# InterfaceBoard.net
KiCad netlist of a schematic drawn in EAGLE
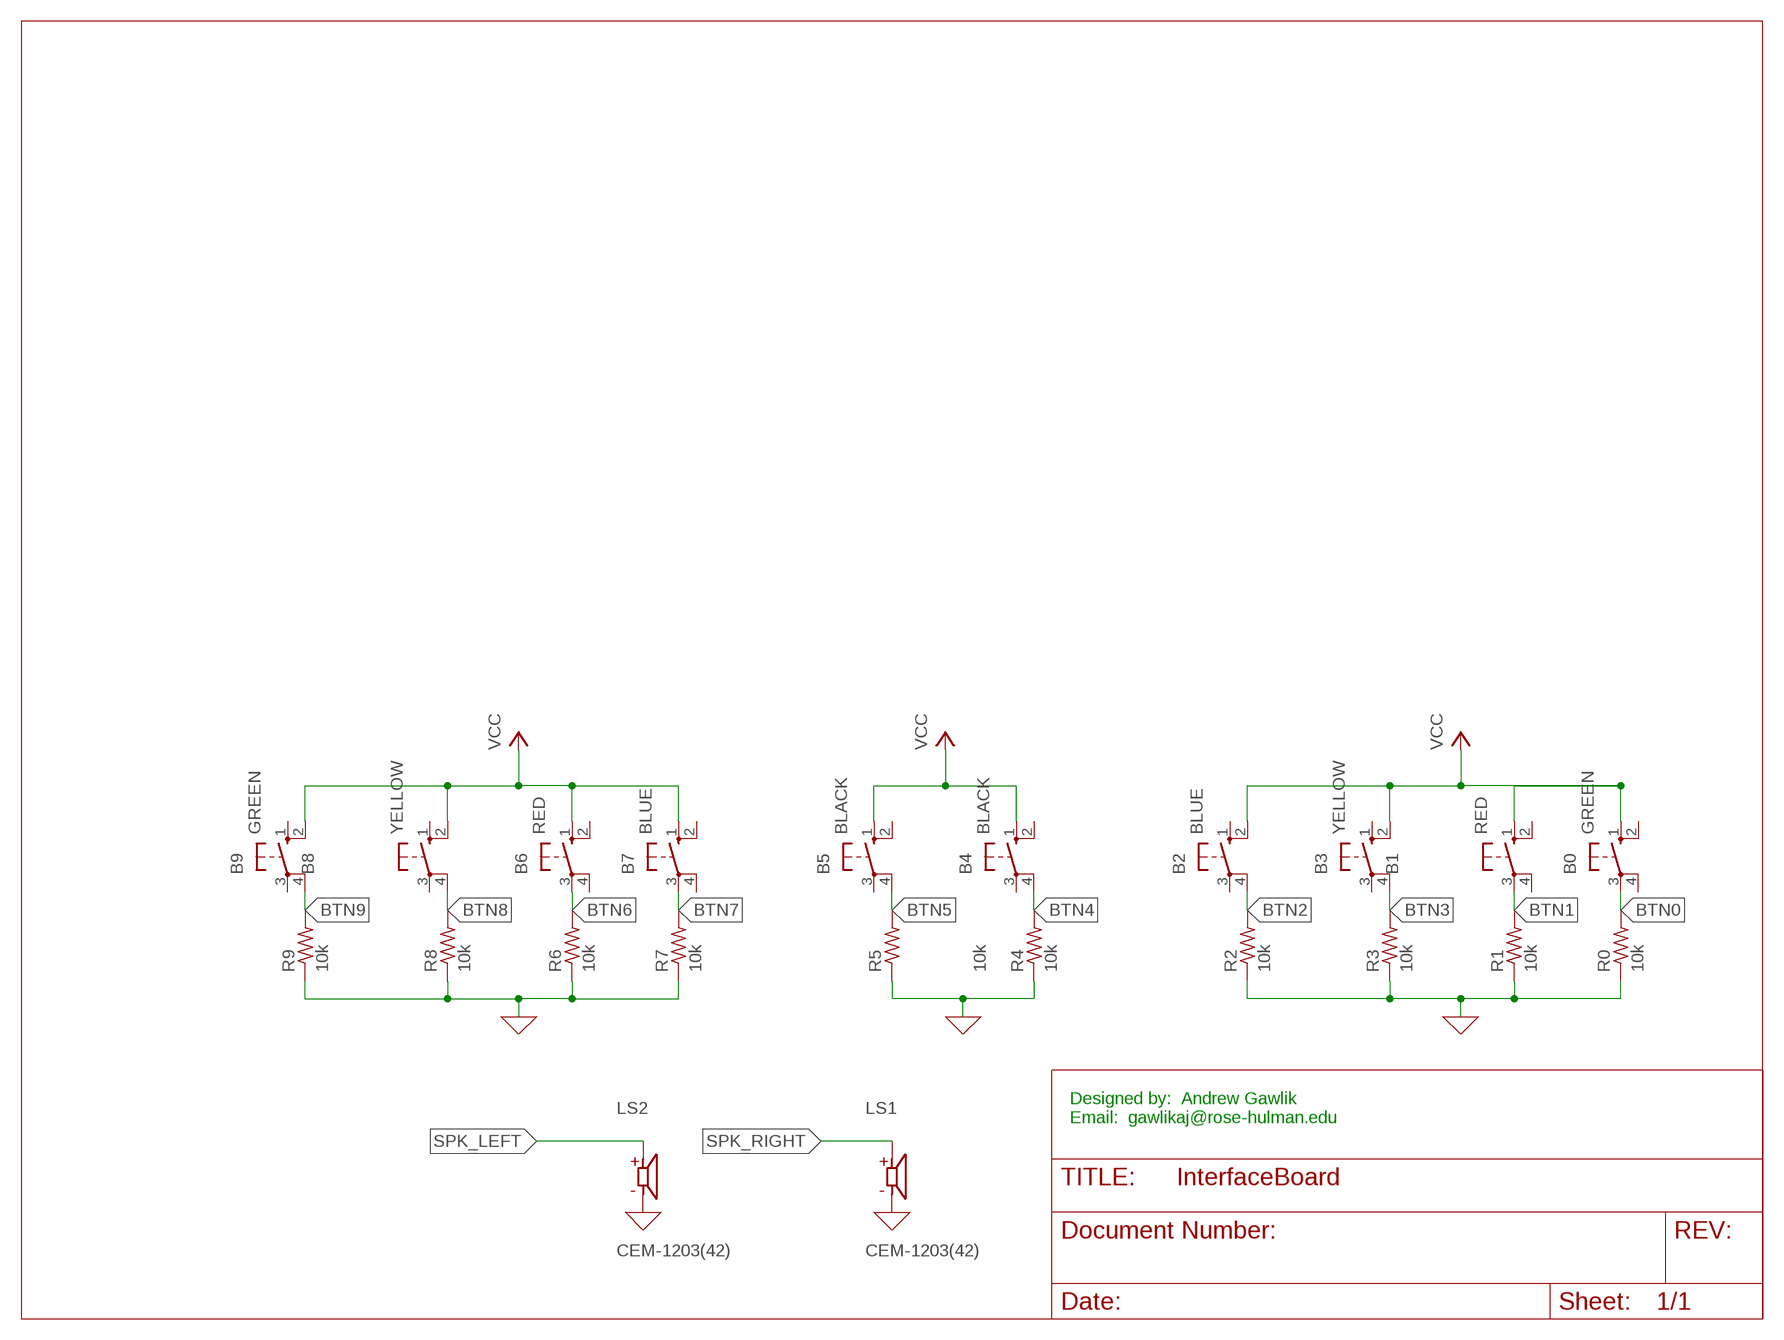
[diagram p0: schematic, sheet 1]

(export (version "E")
  (design (tool "Eeschema 10.0.6"))
  (components
    (comp (ref "B0")
      (value "GREEN")
      (footprint "eagle-import:B3F-10XX")
      (fields (field (name "MPN") "B3F-1000"))
      (libsource (lib "eagle-import") (part "10-XX"))
    )
    (comp (ref "B1")
      (value "RED")
      (footprint "eagle-import:B3F-10XX")
      (fields (field (name "MPN") "B3F-1000"))
      (libsource (lib "eagle-import") (part "10-XX"))
    )
    (comp (ref "B2")
      (value "BLUE")
      (footprint "eagle-import:B3F-10XX")
      (fields (field (name "MPN") "B3F-1000"))
      (libsource (lib "eagle-import") (part "10-XX"))
    )
    (comp (ref "B3")
      (value "YELLOW")
      (footprint "eagle-import:B3F-10XX")
      (fields (field (name "MPN") "B3F-1000"))
      (libsource (lib "eagle-import") (part "10-XX"))
    )
    (comp (ref "B4")
      (value "BLACK")
      (footprint "eagle-import:B3F-10XX")
      (fields (field (name "MPN") "B3F-1000"))
      (libsource (lib "eagle-import") (part "10-XX"))
    )
    (comp (ref "B5")
      (value "BLACK")
      (footprint "eagle-import:B3F-10XX")
      (fields (field (name "MPN") "B3F-1000"))
      (libsource (lib "eagle-import") (part "10-XX"))
    )
    (comp (ref "B6")
      (value "RED")
      (footprint "eagle-import:B3F-10XX")
      (fields (field (name "MPN") "B3F-1000"))
      (libsource (lib "eagle-import") (part "10-XX"))
    )
    (comp (ref "B7")
      (value "BLUE")
      (footprint "eagle-import:B3F-10XX")
      (fields (field (name "MPN") "B3F-1000"))
      (libsource (lib "eagle-import") (part "10-XX"))
    )
    (comp (ref "B8")
      (value "YELLOW")
      (footprint "eagle-import:B3F-10XX")
      (fields (field (name "MPN") "B3F-1000"))
      (libsource (lib "eagle-import") (part "10-XX"))
    )
    (comp (ref "B9")
      (value "GREEN")
      (footprint "eagle-import:B3F-10XX")
      (fields (field (name "MPN") "B3F-1000"))
      (libsource (lib "eagle-import") (part "10-XX"))
    )
    (comp (ref "LS1")
      (value "CEM-1203(42)")
      (footprint "eagle-import:CUI_CEM-1203(42)")
      (fields (field (name "MF") "CUI Devices"))
      (libsource (lib "eagle-import") (part "CEM-1203(42)"))
    )
    (comp (ref "LS2")
      (value "CEM-1203(42)")
      (footprint "eagle-import:CUI_CEM-1203(42)")
      (fields (field (name "MF") "CUI Devices"))
      (libsource (lib "eagle-import") (part "CEM-1203(42)"))
    )
    (comp (ref "R0")
      (value "10k")
      (footprint "eagle-import:0204_5")
      (libsource (lib "eagle-import") (part "R-US_0204/5"))
    )
    (comp (ref "R1")
      (value "10k")
      (footprint "eagle-import:0204_5")
      (libsource (lib "eagle-import") (part "R-US_0204/5"))
    )
    (comp (ref "R2")
      (value "10k")
      (footprint "eagle-import:0204_5")
      (libsource (lib "eagle-import") (part "R-US_0204/5"))
    )
    (comp (ref "R3")
      (value "10k")
      (footprint "eagle-import:0204_5")
      (libsource (lib "eagle-import") (part "R-US_0204/5"))
    )
    (comp (ref "R4")
      (value "10k")
      (footprint "eagle-import:0204_5")
      (libsource (lib "eagle-import") (part "R-US_0204/5"))
    )
    (comp (ref "R5")
      (value "10k")
      (footprint "eagle-import:0204_5")
      (libsource (lib "eagle-import") (part "R-US_0204/5"))
    )
    (comp (ref "R6")
      (value "10k")
      (footprint "eagle-import:0204_5")
      (libsource (lib "eagle-import") (part "R-US_0204/5"))
    )
    (comp (ref "R7")
      (value "10k")
      (footprint "eagle-import:0204_5")
      (libsource (lib "eagle-import") (part "R-US_0204/5"))
    )
    (comp (ref "R8")
      (value "10k")
      (footprint "eagle-import:0204_5")
      (libsource (lib "eagle-import") (part "R-US_0204/5"))
    )
    (comp (ref "R9")
      (value "10k")
      (footprint "eagle-import:0204_5")
      (libsource (lib "eagle-import") (part "R-US_0204/5"))
    )
  )
  (nets
    (net (code "1") (name "BTN0") (class "Default")
      (node (ref "B0") (pin "3") (pinfunction "P_3") (pintype "passive"))
      (node (ref "R0") (pin "2") (pinfunction "2_2") (pintype "passive"))
    )
    (net (code "2") (name "BTN1") (class "Default")
      (node (ref "B1") (pin "3") (pinfunction "P_3") (pintype "passive"))
      (node (ref "R1") (pin "2") (pinfunction "2_2") (pintype "passive"))
    )
    (net (code "3") (name "BTN2") (class "Default")
      (node (ref "B2") (pin "4") (pinfunction "P1_4") (pintype "passive"))
      (node (ref "R2") (pin "2") (pinfunction "2_2") (pintype "passive"))
    )
    (net (code "4") (name "BTN3") (class "Default")
      (node (ref "B3") (pin "4") (pinfunction "P1_4") (pintype "passive"))
      (node (ref "R3") (pin "2") (pinfunction "2_2") (pintype "passive"))
    )
    (net (code "5") (name "BTN4") (class "Default")
      (node (ref "B4") (pin "4") (pinfunction "P1_4") (pintype "passive"))
      (node (ref "R4") (pin "2") (pinfunction "2_2") (pintype "passive"))
    )
    (net (code "6") (name "BTN5") (class "Default")
      (node (ref "B5") (pin "4") (pinfunction "P1_4") (pintype "passive"))
      (node (ref "R5") (pin "2") (pinfunction "2_2") (pintype "passive"))
    )
    (net (code "7") (name "BTN6") (class "Default")
      (node (ref "B6") (pin "3") (pinfunction "P_3") (pintype "passive"))
      (node (ref "R6") (pin "2") (pinfunction "2_2") (pintype "passive"))
    )
    (net (code "8") (name "BTN7") (class "Default")
      (node (ref "B7") (pin "3") (pinfunction "P_3") (pintype "passive"))
      (node (ref "R7") (pin "2") (pinfunction "2_2") (pintype "passive"))
    )
    (net (code "9") (name "BTN8") (class "Default")
      (node (ref "B8") (pin "4") (pinfunction "P1_4") (pintype "passive"))
      (node (ref "R8") (pin "2") (pinfunction "2_2") (pintype "passive"))
    )
    (net (code "10") (name "BTN9") (class "Default")
      (node (ref "B9") (pin "4") (pinfunction "P1_4") (pintype "passive"))
      (node (ref "R9") (pin "2") (pinfunction "2_2") (pintype "passive"))
    )
    (net (code "11") (name "GND") (class "Default")
      (node (ref "LS1") (pin "N") (pinfunction "N_N") (pintype "passive"))
      (node (ref "LS2") (pin "N") (pinfunction "N_N") (pintype "passive"))
      (node (ref "R0") (pin "1") (pinfunction "1_1") (pintype "passive"))
      (node (ref "R1") (pin "1") (pinfunction "1_1") (pintype "passive"))
      (node (ref "R2") (pin "1") (pinfunction "1_1") (pintype "passive"))
      (node (ref "R3") (pin "1") (pinfunction "1_1") (pintype "passive"))
      (node (ref "R4") (pin "1") (pinfunction "1_1") (pintype "passive"))
      (node (ref "R5") (pin "1") (pinfunction "1_1") (pintype "passive"))
      (node (ref "R6") (pin "1") (pinfunction "1_1") (pintype "passive"))
      (node (ref "R7") (pin "1") (pinfunction "1_1") (pintype "passive"))
      (node (ref "R8") (pin "1") (pinfunction "1_1") (pintype "passive"))
      (node (ref "R9") (pin "1") (pinfunction "1_1") (pintype "passive"))
    )
    (net (code "12") (name "SPK_LEFT") (class "Default")
      (node (ref "LS2") (pin "P") (pinfunction "P_P") (pintype "passive"))
    )
    (net (code "13") (name "SPK_RIGHT") (class "Default")
      (node (ref "LS1") (pin "P") (pinfunction "P_P") (pintype "passive"))
    )
    (net (code "14") (name "VCC") (class "Default")
      (node (ref "B0") (pin "1") (pinfunction "S_1") (pintype "passive"))
      (node (ref "B1") (pin "1") (pinfunction "S_1") (pintype "passive"))
      (node (ref "B2") (pin "2") (pinfunction "S1_2") (pintype "passive"))
      (node (ref "B3") (pin "2") (pinfunction "S1_2") (pintype "passive"))
      (node (ref "B4") (pin "1") (pinfunction "S_1") (pintype "passive"))
      (node (ref "B5") (pin "1") (pinfunction "S_1") (pintype "passive"))
      (node (ref "B6") (pin "1") (pinfunction "S_1") (pintype "passive"))
      (node (ref "B7") (pin "1") (pinfunction "S_1") (pintype "passive"))
      (node (ref "B8") (pin "2") (pinfunction "S1_2") (pintype "passive"))
      (node (ref "B9") (pin "2") (pinfunction "S1_2") (pintype "passive"))
    )
    (net (code "15") (name "unconnected-(B0-P1-Pad4)") (class "Default")
      (node (ref "B0") (pin "4") (pinfunction "P1_4") (pintype "passive"))
    )
    (net (code "16") (name "unconnected-(B0-S1-Pad2)") (class "Default")
      (node (ref "B0") (pin "2") (pinfunction "S1_2") (pintype "passive"))
    )
    (net (code "17") (name "unconnected-(B1-P1-Pad4)") (class "Default")
      (node (ref "B1") (pin "4") (pinfunction "P1_4") (pintype "passive"))
    )
    (net (code "18") (name "unconnected-(B1-S1-Pad2)") (class "Default")
      (node (ref "B1") (pin "2") (pinfunction "S1_2") (pintype "passive"))
    )
    (net (code "19") (name "unconnected-(B2-P-Pad3)") (class "Default")
      (node (ref "B2") (pin "3") (pinfunction "P_3") (pintype "passive"))
    )
    (net (code "20") (name "unconnected-(B2-S-Pad1)") (class "Default")
      (node (ref "B2") (pin "1") (pinfunction "S_1") (pintype "passive"))
    )
    (net (code "21") (name "unconnected-(B3-P-Pad3)") (class "Default")
      (node (ref "B3") (pin "3") (pinfunction "P_3") (pintype "passive"))
    )
    (net (code "22") (name "unconnected-(B3-S-Pad1)") (class "Default")
      (node (ref "B3") (pin "1") (pinfunction "S_1") (pintype "passive"))
    )
    (net (code "23") (name "unconnected-(B4-P-Pad3)") (class "Default")
      (node (ref "B4") (pin "3") (pinfunction "P_3") (pintype "passive"))
    )
    (net (code "24") (name "unconnected-(B4-S1-Pad2)") (class "Default")
      (node (ref "B4") (pin "2") (pinfunction "S1_2") (pintype "passive"))
    )
    (net (code "25") (name "unconnected-(B5-P-Pad3)") (class "Default")
      (node (ref "B5") (pin "3") (pinfunction "P_3") (pintype "passive"))
    )
    (net (code "26") (name "unconnected-(B5-S1-Pad2)") (class "Default")
      (node (ref "B5") (pin "2") (pinfunction "S1_2") (pintype "passive"))
    )
    (net (code "27") (name "unconnected-(B6-P1-Pad4)") (class "Default")
      (node (ref "B6") (pin "4") (pinfunction "P1_4") (pintype "passive"))
    )
    (net (code "28") (name "unconnected-(B6-S1-Pad2)") (class "Default")
      (node (ref "B6") (pin "2") (pinfunction "S1_2") (pintype "passive"))
    )
    (net (code "29") (name "unconnected-(B7-P1-Pad4)") (class "Default")
      (node (ref "B7") (pin "4") (pinfunction "P1_4") (pintype "passive"))
    )
    (net (code "30") (name "unconnected-(B7-S1-Pad2)") (class "Default")
      (node (ref "B7") (pin "2") (pinfunction "S1_2") (pintype "passive"))
    )
    (net (code "31") (name "unconnected-(B8-P-Pad3)") (class "Default")
      (node (ref "B8") (pin "3") (pinfunction "P_3") (pintype "passive"))
    )
    (net (code "32") (name "unconnected-(B8-S-Pad1)") (class "Default")
      (node (ref "B8") (pin "1") (pinfunction "S_1") (pintype "passive"))
    )
    (net (code "33") (name "unconnected-(B9-P-Pad3)") (class "Default")
      (node (ref "B9") (pin "3") (pinfunction "P_3") (pintype "passive"))
    )
    (net (code "34") (name "unconnected-(B9-S-Pad1)") (class "Default")
      (node (ref "B9") (pin "1") (pinfunction "S_1") (pintype "passive"))
    )
  )
)
